# BEP2_rev1_seeed.net
KiCad netlist of a schematic drawn in EAGLE
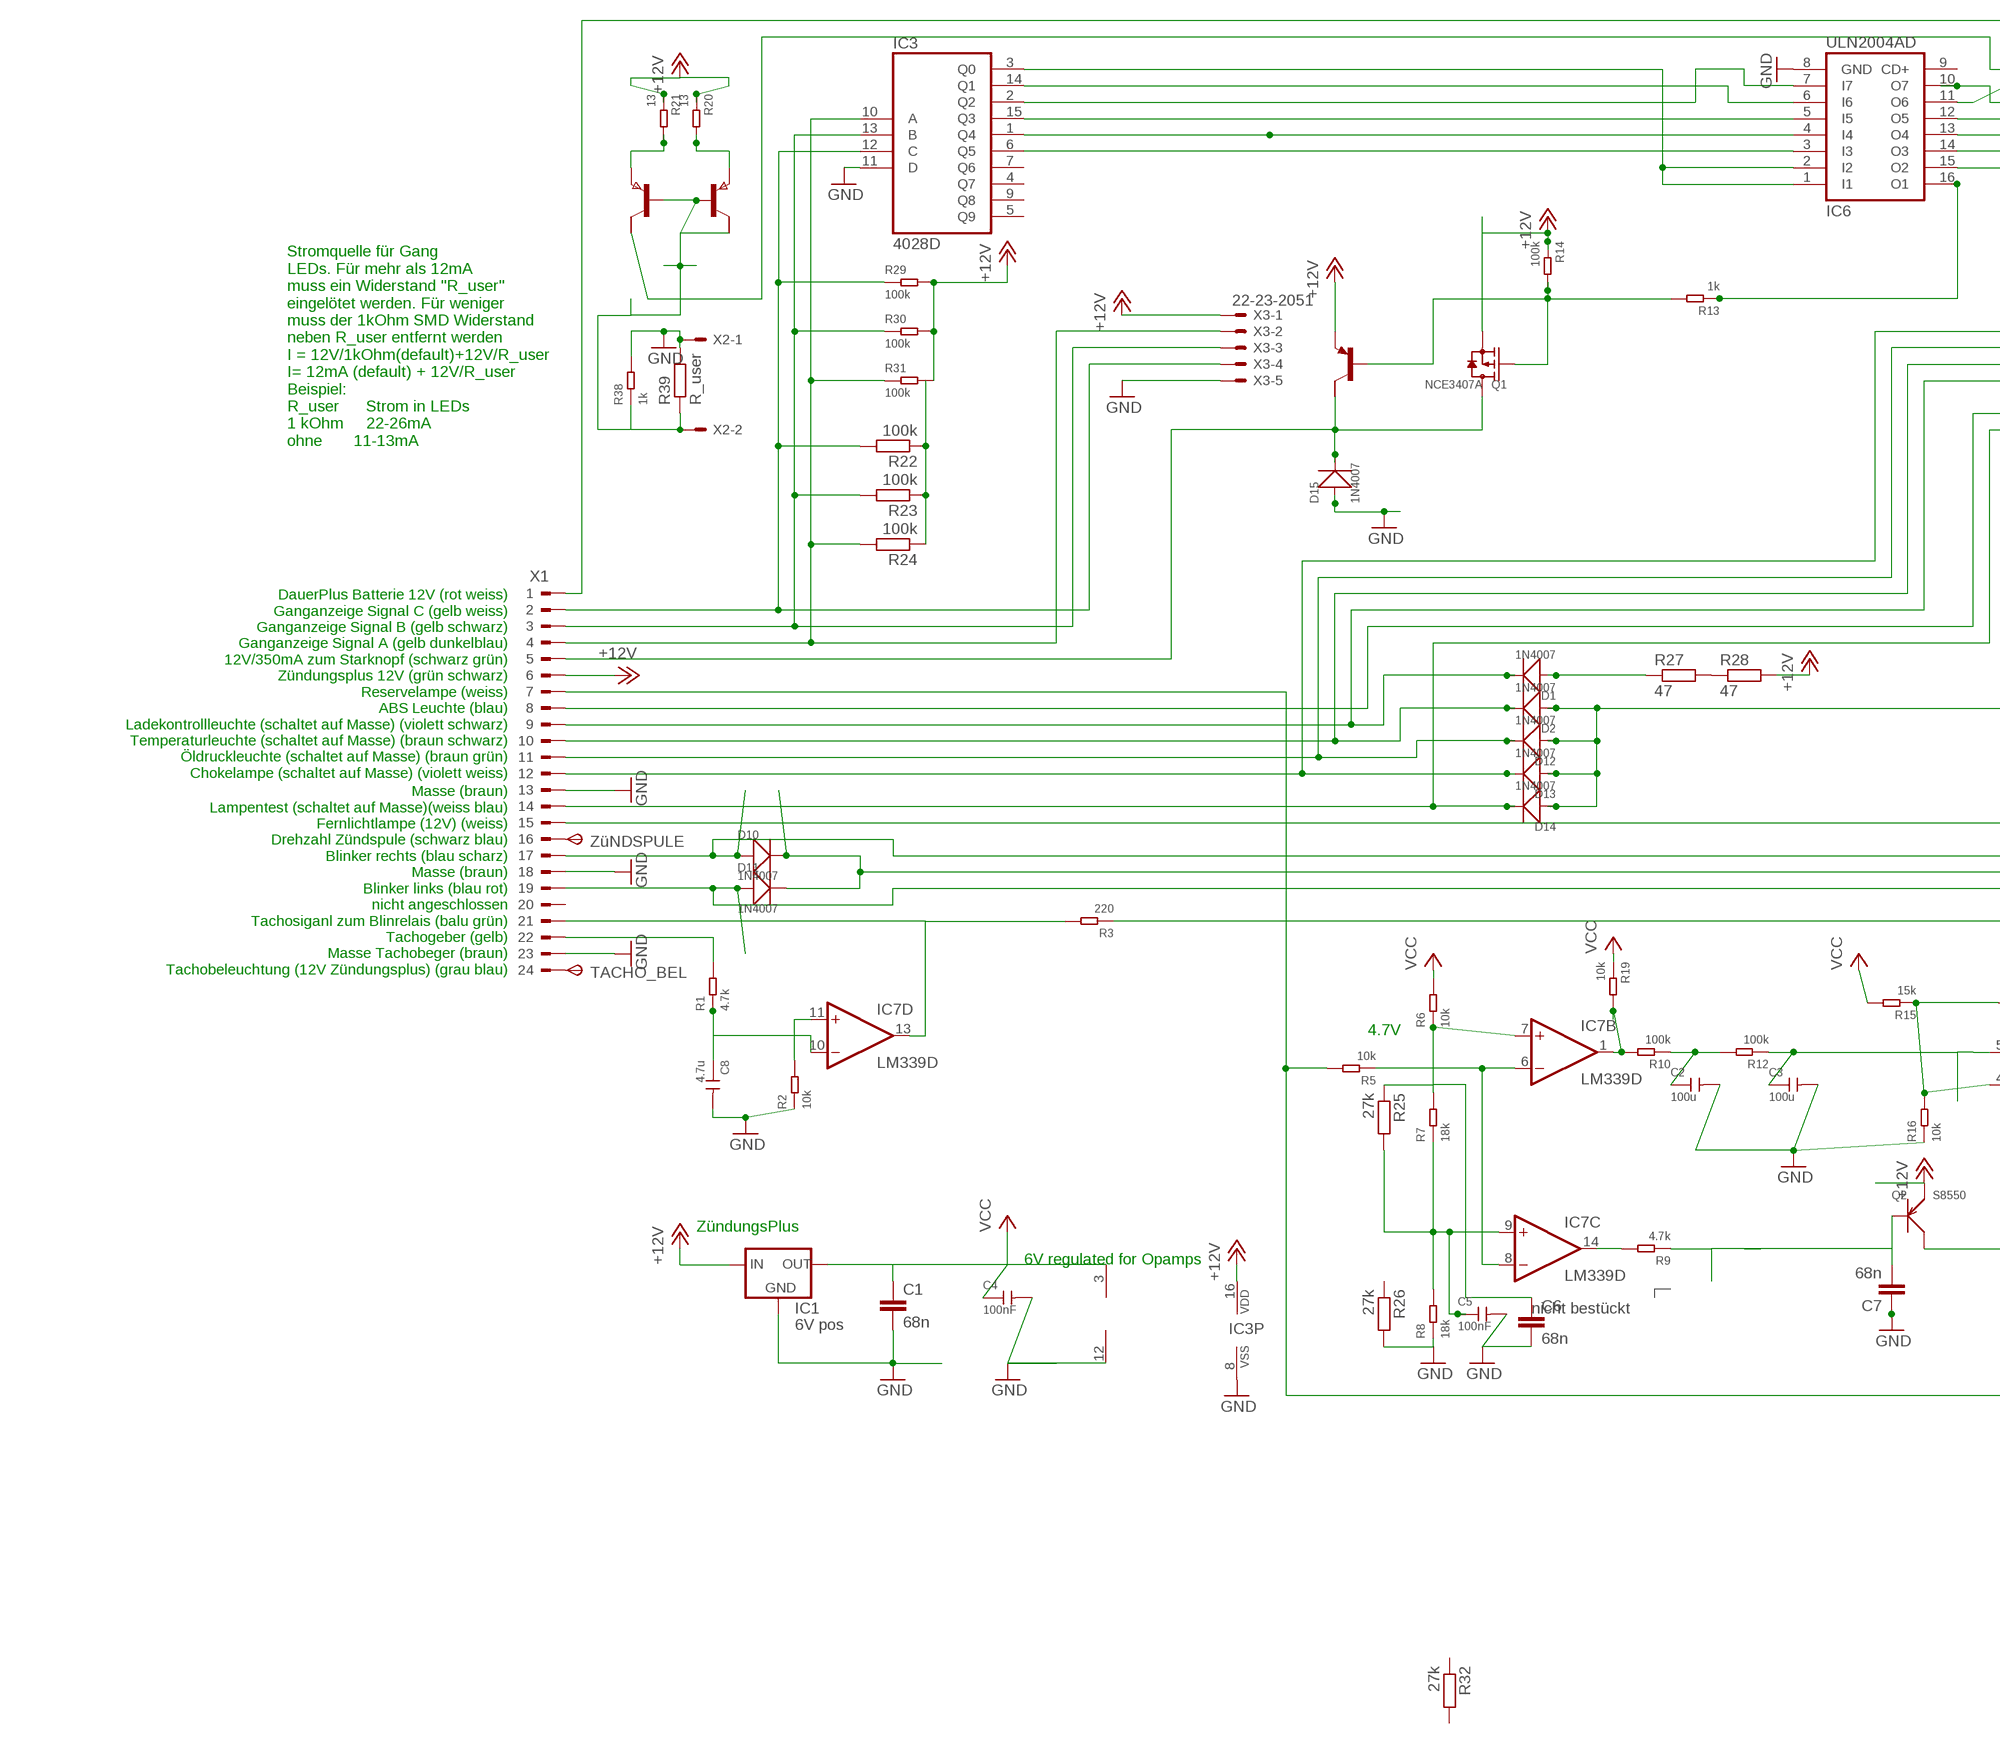
[diagram p0: schematic, sheet 1, part 1 of 2]
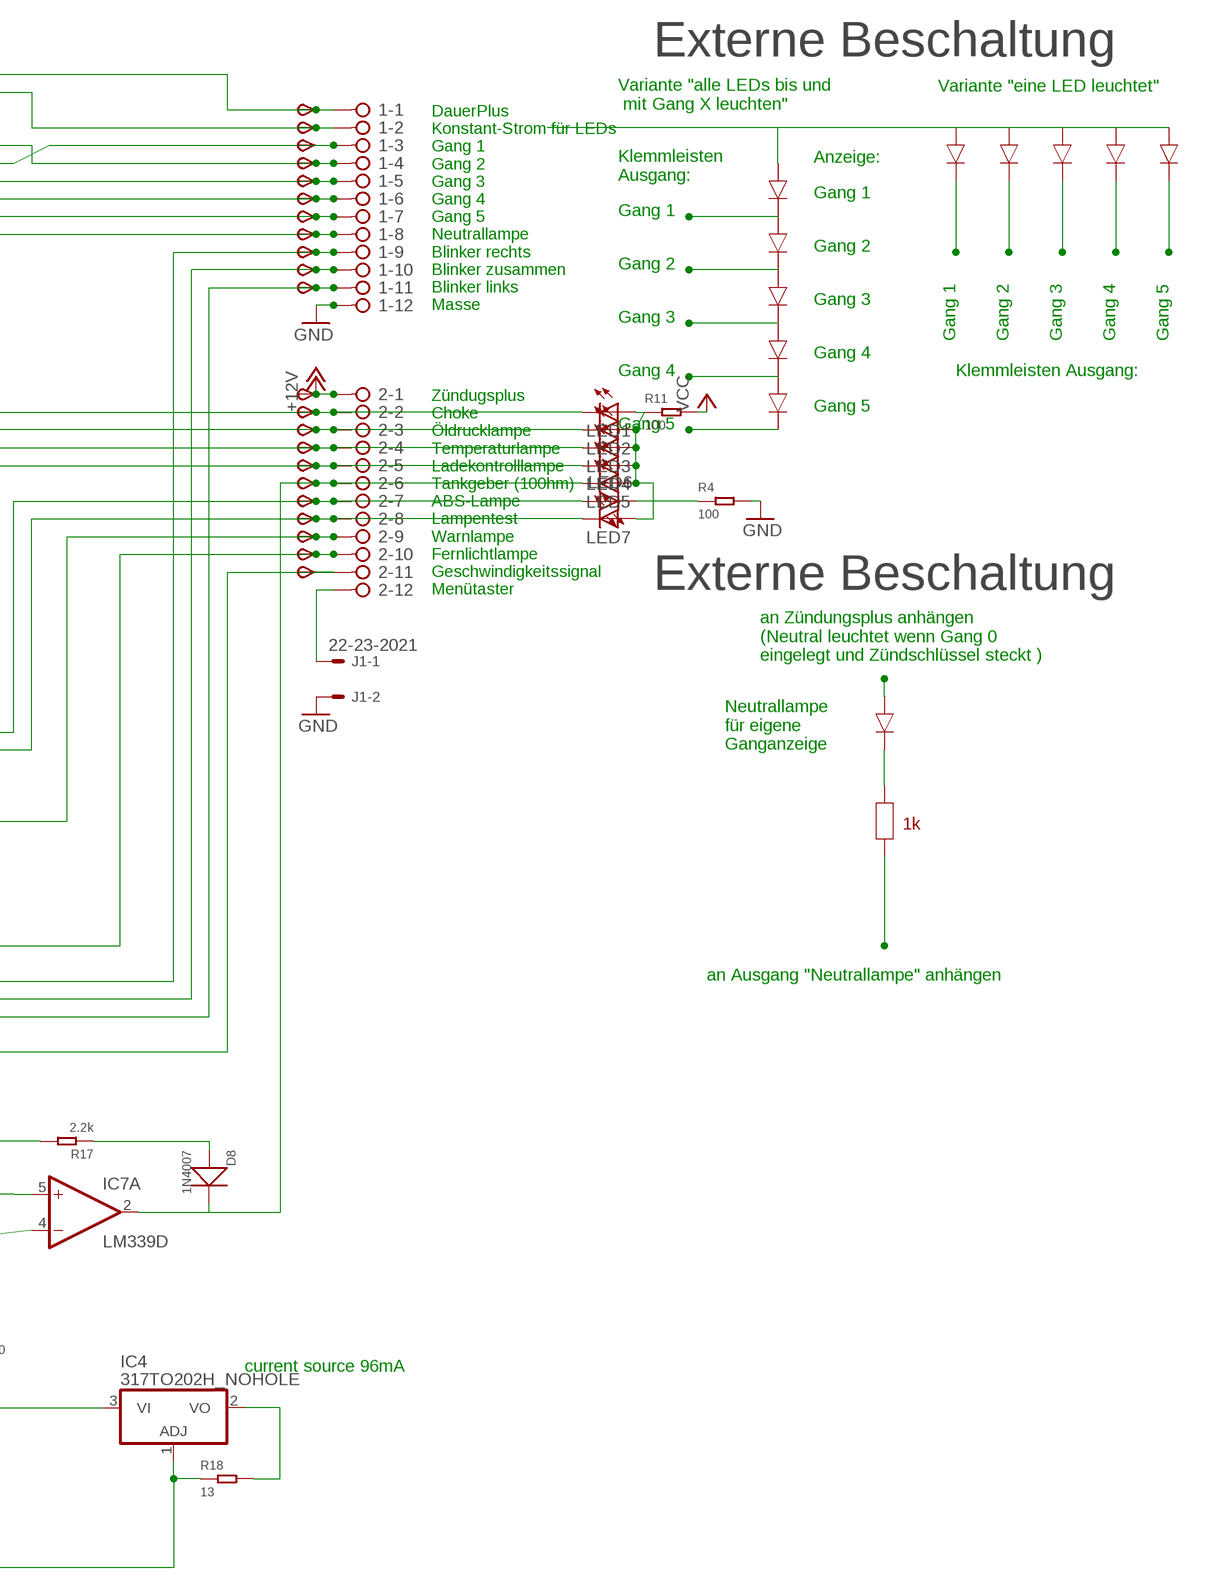
[diagram p1: schematic, sheet 1, part 2 of 2]

(export (version "E")
  (design (tool "Eeschema 10.0.6"))
  (components
    (comp (ref "1")
      (value "2081-1132")
      (footprint "eagle-import:12-PIN")
      (libsource (lib "eagle-import") (part "2081-1132"))
    )
    (comp (ref "2")
      (value "2081-1132")
      (footprint "eagle-import:12-PIN")
      (libsource (lib "eagle-import") (part "2081-1132"))
    )
    (comp (ref "C1")
      (value "68n")
      (footprint "eagle-import:C1206K")
      (libsource (lib "eagle-import") (part "C-EUC1206K"))
    )
    (comp (ref "C2")
      (value "100u")
      (footprint "eagle-import:C1206")
      (fields (field (name "MPN") "GRM31CR60J107ME39L"))
      (libsource (lib "eagle-import") (part "CERAMIC-100UF-6.3V-20%-X5R(1206)"))
    )
    (comp (ref "C3")
      (value "100u")
      (footprint "eagle-import:C1206")
      (fields (field (name "MPN") "GRM31CR60J107ME39L"))
      (libsource (lib "eagle-import") (part "CERAMIC-100UF-6.3V-20%-X5R(1206)"))
    )
    (comp (ref "C4")
      (value "100nF")
      (footprint "eagle-import:C0805")
      (fields (field (name "MPN") "CC0805KRX7R9BB104"))
      (libsource (lib "eagle-import") (part "CERAMIC-100NF-50V-10%-X7R(0805)"))
    )
    (comp (ref "C5")
      (value "100nF")
      (footprint "eagle-import:C0805")
      (fields (field (name "MPN") "CC0805KRX7R9BB104"))
      (libsource (lib "eagle-import") (part "CERAMIC-100NF-50V-10%-X7R(0805)"))
    )
    (comp (ref "C6")
      (value "68n")
      (footprint "eagle-import:C1206K")
      (libsource (lib "eagle-import") (part "C-EUC1206K"))
    )
    (comp (ref "C7")
      (value "68n")
      (footprint "eagle-import:C1206K")
      (libsource (lib "eagle-import") (part "C-EUC1206K"))
    )
    (comp (ref "C8")
      (value "4.7u")
      (footprint "eagle-import:C0805")
      (fields (field (name "MPN") "CC0805KKX5R8BB475"))
      (libsource (lib "eagle-import") (part "CERAMIC-4.7UF-25V-10%-X5R(0805)"))
    )
    (comp (ref "D1")
      (value "1N4007")
      (footprint "eagle-import:DO-214AC")
      (libsource (lib "eagle-import") (part "DIODE-GEN-PURPOSE-1KV-1A(DO-214AC)"))
    )
    (comp (ref "D2")
      (value "1N4007")
      (footprint "eagle-import:DO-214AC")
      (libsource (lib "eagle-import") (part "DIODE-GEN-PURPOSE-1KV-1A(DO-214AC)"))
    )
    (comp (ref "D8")
      (value "1N4007")
      (footprint "eagle-import:DO-214AC")
      (libsource (lib "eagle-import") (part "DIODE-GEN-PURPOSE-1KV-1A(DO-214AC)"))
    )
    (comp (ref "D10")
      (value "1N4007")
      (footprint "eagle-import:DO-214AC")
      (libsource (lib "eagle-import") (part "DIODE-GEN-PURPOSE-1KV-1A(DO-214AC)"))
    )
    (comp (ref "D11")
      (value "1N4007")
      (footprint "eagle-import:DO-214AC")
      (libsource (lib "eagle-import") (part "DIODE-GEN-PURPOSE-1KV-1A(DO-214AC)"))
    )
    (comp (ref "D12")
      (value "1N4007")
      (footprint "eagle-import:DO-214AC")
      (libsource (lib "eagle-import") (part "DIODE-GEN-PURPOSE-1KV-1A(DO-214AC)"))
    )
    (comp (ref "D13")
      (value "1N4007")
      (footprint "eagle-import:DO-214AC")
      (libsource (lib "eagle-import") (part "DIODE-GEN-PURPOSE-1KV-1A(DO-214AC)"))
    )
    (comp (ref "D14")
      (value "1N4007")
      (footprint "eagle-import:DO-214AC")
      (libsource (lib "eagle-import") (part "DIODE-GEN-PURPOSE-1KV-1A(DO-214AC)"))
    )
    (comp (ref "D15")
      (value "1N4007")
      (footprint "eagle-import:DO-214AC")
      (libsource (lib "eagle-import") (part "DIODE-GEN-PURPOSE-1KV-1A(DO-214AC)"))
    )
    (comp (ref "IC1")
      (value "6V pos")
      (footprint "eagle-import:78LXX")
      (libsource (lib "eagle-import") (part "78LXX"))
    )
    (comp (ref "IC3")
      (value "4028D")
      (footprint "eagle-import:SO16")
      (libsource (lib "eagle-import") (part "4028D"))
    )
    (comp (ref "IC4")
      (value "317TO202H_NOHOLE")
      (footprint "eagle-import:TO220H_NOHOLE")
      (libsource (lib "eagle-import") (part "317TO202H_NOHOLE"))
    )
    (comp (ref "IC6")
      (value "ULN2004AD")
      (footprint "eagle-import:SO16")
      (libsource (lib "eagle-import") (part "ULN2004AD"))
    )
    (comp (ref "IC7")
      (value "LM339D")
      (footprint "eagle-import:SO14")
      (libsource (lib "eagle-import") (part "LM339D"))
    )
    (comp (ref "J1")
      (value "22-23-2021")
      (footprint "eagle-import:22-23-2021")
      (fields (field (name "MF") "MOLEX"))
      (libsource (lib "eagle-import") (part "con_Molex_BMW_22-23-2021"))
    )
    (comp (ref "LED1")
      (value "LEDLD260")
      (footprint "eagle-import:LD260")
      (libsource (lib "eagle-import") (part "LEDLD260"))
    )
    (comp (ref "LED2")
      (value "LEDLD260")
      (footprint "eagle-import:LD260")
      (libsource (lib "eagle-import") (part "LEDLD260"))
    )
    (comp (ref "LED3")
      (value "LEDLD260")
      (footprint "eagle-import:LD260")
      (libsource (lib "eagle-import") (part "LEDLD260"))
    )
    (comp (ref "LED4")
      (value "LEDLD260")
      (footprint "eagle-import:LD260")
      (libsource (lib "eagle-import") (part "LEDLD260"))
    )
    (comp (ref "LED5")
      (value "LEDLD260")
      (footprint "eagle-import:LD260")
      (libsource (lib "eagle-import") (part "LEDLD260"))
    )
    (comp (ref "LED6")
      (value "LEDLD260")
      (footprint "eagle-import:LD260")
      (libsource (lib "eagle-import") (part "LEDLD260"))
    )
    (comp (ref "LED7")
      (value "LEDLD260")
      (footprint "eagle-import:LD260")
      (libsource (lib "eagle-import") (part "LEDLD260"))
    )
    (comp (ref "Q1")
      (value "NCE3407A")
      (footprint "eagle-import:SOT-23")
      (libsource (lib "eagle-import") (part "SMD-MOSFET-P-CH-VDC=30V-ID=4.3A-NCE3407A(SOT-23)"))
    )
    (comp (ref "Q2")
      (value "S8550")
      (footprint "eagle-import:SOT-23")
      (libsource (lib "eagle-import") (part "SMD-TRANSISTORS-PNP-25V-500MA-S8550(SOT-23)"))
    )
    (comp (ref "Q3")
      (value "BCP53T1")
      (footprint "eagle-import:SOT223")
      (libsource (lib "eagle-import") (part "BCP53T1"))
    )
    (comp (ref "R1")
      (value "4.7k")
      (footprint "eagle-import:R0805")
      (fields (field (name "MPN") "RC0805JR-074K7L"))
      (libsource (lib "eagle-import") (part "SMD-RES-4.7K-5%-1/8W(0805)"))
    )
    (comp (ref "R2")
      (value "10k")
      (footprint "eagle-import:R0805")
      (fields (field (name "MPN") "RC0805FR-0710KL"))
      (libsource (lib "eagle-import") (part "SMD-RES-10K-1%-1/8W(0805)"))
    )
    (comp (ref "R3")
      (value "220")
      (footprint "eagle-import:R0805")
      (fields (field (name "MPN") "RC0805JR-07220RL"))
      (libsource (lib "eagle-import") (part "SMD-RES-220R-5%-1/8W(0805)"))
    )
    (comp (ref "R4")
      (value "100")
      (footprint "eagle-import:R0805")
      (fields (field (name "MPN") "RC0805JR-07100RL"))
      (libsource (lib "eagle-import") (part "SMD-RES-100R-5%-1/8W(0805)"))
    )
    (comp (ref "R5")
      (value "10k")
      (footprint "eagle-import:R0805")
      (fields (field (name "MPN") "RC0805FR-0710KL"))
      (libsource (lib "eagle-import") (part "SMD-RES-10K-1%-1/8W(0805)"))
    )
    (comp (ref "R6")
      (value "10k")
      (footprint "eagle-import:R0805")
      (fields (field (name "MPN") "RC0805FR-0710KL"))
      (libsource (lib "eagle-import") (part "SMD-RES-10K-1%-1/8W(0805)"))
    )
    (comp (ref "R7")
      (value "18k")
      (footprint "eagle-import:R0603")
      (fields (field (name "MPN") "RC0603JR-0718KL"))
      (libsource (lib "eagle-import") (part "SMD-RES-18K-5%-1/10W(0603)"))
    )
    (comp (ref "R8")
      (value "18k")
      (footprint "eagle-import:R0603")
      (fields (field (name "MPN") "RC0603JR-0718KL"))
      (libsource (lib "eagle-import") (part "SMD-RES-18K-5%-1/10W(0603)"))
    )
    (comp (ref "R9")
      (value "4.7k")
      (footprint "eagle-import:R0805")
      (fields (field (name "MPN") "RC0805JR-074K7L"))
      (libsource (lib "eagle-import") (part "SMD-RES-4.7K-5%-1/8W(0805)"))
    )
    (comp (ref "R10")
      (value "100k")
      (footprint "eagle-import:R0603")
      (fields (field (name "MPN") "RC0603FR-07100KL"))
      (libsource (lib "eagle-import") (part "SMD-RES-100K-1%-1/10W(0603)"))
    )
    (comp (ref "R11")
      (value "100")
      (footprint "eagle-import:R0805")
      (fields (field (name "MPN") "RC0805JR-07100RL"))
      (libsource (lib "eagle-import") (part "SMD-RES-100R-5%-1/8W(0805)"))
    )
    (comp (ref "R12")
      (value "100k")
      (footprint "eagle-import:R0603")
      (fields (field (name "MPN") "RC0603FR-07100KL"))
      (libsource (lib "eagle-import") (part "SMD-RES-100K-1%-1/10W(0603)"))
    )
    (comp (ref "R13")
      (value "1k")
      (footprint "eagle-import:R0805")
      (fields (field (name "MPN") "RC0805JR-071KL"))
      (libsource (lib "eagle-import") (part "SMD-RES-1K-5%-1/8W(0805)"))
    )
    (comp (ref "R14")
      (value "100k")
      (footprint "eagle-import:R0603")
      (fields (field (name "MPN") "RC0603FR-07100KL"))
      (libsource (lib "eagle-import") (part "SMD-RES-100K-1%-1/10W(0603)"))
    )
    (comp (ref "R15")
      (value "15k")
      (footprint "eagle-import:R0603")
      (fields (field (name "MPN") "RC0603FR-0715KL"))
      (libsource (lib "eagle-import") (part "SMD-RES-15K-1%-1/10W(0603)"))
    )
    (comp (ref "R16")
      (value "10k")
      (footprint "eagle-import:R0805")
      (fields (field (name "MPN") "RC0805FR-0710KL"))
      (libsource (lib "eagle-import") (part "SMD-RES-10K-1%-1/8W(0805)"))
    )
    (comp (ref "R17")
      (value "2.2k")
      (footprint "eagle-import:R0805")
      (fields (field (name "MPN") "RC0805JR-072K2L"))
      (libsource (lib "eagle-import") (part "SMD-RES-2.2K-5%-1/8W(0805)"))
    )
    (comp (ref "R18")
      (value "13")
      (footprint "eagle-import:R1206")
      (fields (field (name "MPN") "RC1206JR-0713RL"))
      (libsource (lib "eagle-import") (part "SMD-RES-13R-5%-1/4W(1206)"))
    )
    (comp (ref "R19")
      (value "10k")
      (footprint "eagle-import:R0805")
      (fields (field (name "MPN") "RC0805FR-0710KL"))
      (libsource (lib "eagle-import") (part "SMD-RES-10K-1%-1/8W(0805)"))
    )
    (comp (ref "R20")
      (value "13")
      (footprint "eagle-import:R1206")
      (fields (field (name "MPN") "RC1206JR-0713RL"))
      (libsource (lib "eagle-import") (part "SMD-RES-13R-5%-1/4W(1206)"))
    )
    (comp (ref "R21")
      (value "13")
      (footprint "eagle-import:R1206")
      (fields (field (name "MPN") "RC1206JR-0713RL"))
      (libsource (lib "eagle-import") (part "SMD-RES-13R-5%-1/4W(1206)"))
    )
    (comp (ref "R22")
      (value "100k")
      (footprint "eagle-import:R0805")
      (libsource (lib "eagle-import") (part "R-EU_R0805"))
    )
    (comp (ref "R23")
      (value "100k")
      (footprint "eagle-import:R0805")
      (libsource (lib "eagle-import") (part "R-EU_R0805"))
    )
    (comp (ref "R24")
      (value "100k")
      (footprint "eagle-import:R0805")
      (libsource (lib "eagle-import") (part "R-EU_R0805"))
    )
    (comp (ref "R25")
      (value "27k")
      (footprint "eagle-import:R0805")
      (libsource (lib "eagle-import") (part "R-EU_R0805"))
    )
    (comp (ref "R26")
      (value "27k")
      (footprint "eagle-import:R0805")
      (libsource (lib "eagle-import") (part "R-EU_R0805"))
    )
    (comp (ref "R27")
      (value "47")
      (footprint "eagle-import:V235_17_1MM")
      (libsource (lib "eagle-import") (part "R-EU_V235/17_1MM"))
    )
    (comp (ref "R28")
      (value "47")
      (footprint "eagle-import:V235_17_1MM")
      (libsource (lib "eagle-import") (part "R-EU_V235/17_1MM"))
    )
    (comp (ref "R29")
      (value "100k")
      (footprint "eagle-import:R0603")
      (fields (field (name "MPN") "RC0603FR-07100KL"))
      (libsource (lib "eagle-import") (part "SMD-RES-100K-1%-1/10W(0603)"))
    )
    (comp (ref "R30")
      (value "100k")
      (footprint "eagle-import:R0603")
      (fields (field (name "MPN") "RC0603FR-07100KL"))
      (libsource (lib "eagle-import") (part "SMD-RES-100K-1%-1/10W(0603)"))
    )
    (comp (ref "R31")
      (value "100k")
      (footprint "eagle-import:R0603")
      (fields (field (name "MPN") "RC0603FR-07100KL"))
      (libsource (lib "eagle-import") (part "SMD-RES-100K-1%-1/10W(0603)"))
    )
    (comp (ref "R32")
      (value "27k")
      (footprint "eagle-import:R0805")
      (libsource (lib "eagle-import") (part "R-EU_R0805"))
    )
    (comp (ref "R38")
      (value "1k")
      (footprint "eagle-import:R0805")
      (fields (field (name "MPN") "RC0805JR-071KL"))
      (libsource (lib "eagle-import") (part "SMD-RES-1K-5%-1/8W(0805)"))
    )
    (comp (ref "R39")
      (value "R_user")
      (footprint "eagle-import:R0805")
      (libsource (lib "eagle-import") (part "R-EU_R0805"))
    )
    (comp (ref "T1")
      (value "PNP2SM8")
      (footprint "eagle-import:SM8")
      (libsource (lib "eagle-import") (part "PNP2SM8"))
    )
    (comp (ref "TACHO_BEL")
      (value "TPSP1_1MM")
      (footprint "eagle-import:P1_1.0MM")
      (libsource (lib "eagle-import") (part "TPSP1_1MM"))
    )
    (comp (ref "TP1")
      (value "TPSB1.8")
      (footprint "eagle-import:B1.8")
      (libsource (lib "eagle-import") (part "TPSB1.8"))
    )
    (comp (ref "TP2")
      (value "TPSB1.8")
      (footprint "eagle-import:B1.8")
      (libsource (lib "eagle-import") (part "TPSB1.8"))
    )
    (comp (ref "TP3")
      (value "TPSB1.8")
      (footprint "eagle-import:B1.8")
      (libsource (lib "eagle-import") (part "TPSB1.8"))
    )
    (comp (ref "TP4")
      (value "TPSB1.8")
      (footprint "eagle-import:B1.8")
      (libsource (lib "eagle-import") (part "TPSB1.8"))
    )
    (comp (ref "TP5")
      (value "TPSB1.8")
      (footprint "eagle-import:B1.8")
      (libsource (lib "eagle-import") (part "TPSB1.8"))
    )
    (comp (ref "TP6")
      (value "TPSB1.8")
      (footprint "eagle-import:B1.8")
      (libsource (lib "eagle-import") (part "TPSB1.8"))
    )
    (comp (ref "TP7")
      (value "TPSB1.8")
      (footprint "eagle-import:B1.8")
      (libsource (lib "eagle-import") (part "TPSB1.8"))
    )
    (comp (ref "TP8")
      (value "TPSB1.8")
      (footprint "eagle-import:B1.8")
      (libsource (lib "eagle-import") (part "TPSB1.8"))
    )
    (comp (ref "TP9")
      (value "TPSB1.8")
      (footprint "eagle-import:B1.8")
      (libsource (lib "eagle-import") (part "TPSB1.8"))
    )
    (comp (ref "TP10")
      (value "TPSB1.8")
      (footprint "eagle-import:B1.8")
      (libsource (lib "eagle-import") (part "TPSB1.8"))
    )
    (comp (ref "TP11")
      (value "TPSB1.8")
      (footprint "eagle-import:B1.8")
      (libsource (lib "eagle-import") (part "TPSB1.8"))
    )
    (comp (ref "TP12")
      (value "TPSB1.8")
      (footprint "eagle-import:B1.8")
      (libsource (lib "eagle-import") (part "TPSB1.8"))
    )
    (comp (ref "TP16")
      (value "TPSB1.8")
      (footprint "eagle-import:B1.8")
      (libsource (lib "eagle-import") (part "TPSB1.8"))
    )
    (comp (ref "TP17")
      (value "TPSB1.8")
      (footprint "eagle-import:B1.8")
      (libsource (lib "eagle-import") (part "TPSB1.8"))
    )
    (comp (ref "TP18")
      (value "TPSB1.8")
      (footprint "eagle-import:B1.8")
      (libsource (lib "eagle-import") (part "TPSB1.8"))
    )
    (comp (ref "TP19")
      (value "TPSB1.8")
      (footprint "eagle-import:B1.8")
      (libsource (lib "eagle-import") (part "TPSB1.8"))
    )
    (comp (ref "TP21")
      (value "TPSB1.8")
      (footprint "eagle-import:B1.8")
      (libsource (lib "eagle-import") (part "TPSB1.8"))
    )
    (comp (ref "TP22")
      (value "TPSB1.8")
      (footprint "eagle-import:B1.8")
      (libsource (lib "eagle-import") (part "TPSB1.8"))
    )
    (comp (ref "TP23")
      (value "TPSB1.8")
      (footprint "eagle-import:B1.8")
      (libsource (lib "eagle-import") (part "TPSB1.8"))
    )
    (comp (ref "TP24")
      (value "TPSB1,27")
      (footprint "eagle-import:B1,27")
      (libsource (lib "eagle-import") (part "TPSB1,27"))
    )
    (comp (ref "TP25")
      (value "TPSB1.8")
      (footprint "eagle-import:B1.8")
      (libsource (lib "eagle-import") (part "TPSB1.8"))
    )
    (comp (ref "TP26")
      (value "TPSB1.8")
      (footprint "eagle-import:B1.8")
      (libsource (lib "eagle-import") (part "TPSB1.8"))
    )
    (comp (ref "X1")
      (value "CON_BMW")
      (footprint "eagle-import:24-PIN")
      (libsource (lib "eagle-import") (part "CON_BMW"))
    )
    (comp (ref "X2")
      (value "22-23-2021")
      (footprint "eagle-import:22-23-2021")
      (fields (field (name "MF") "MOLEX"))
      (libsource (lib "eagle-import") (part "22-23-2021"))
    )
    (comp (ref "X3")
      (value "22-23-2051")
      (footprint "eagle-import:22-23-2051")
      (fields (field (name "MF") "MOLEX"))
      (libsource (lib "eagle-import") (part "22-23-2051"))
    )
    (comp (ref "ZüNDSPULE")
      (value "TPSP1_1MM")
      (footprint "eagle-import:P1_1.0MM")
      (libsource (lib "eagle-import") (part "TPSP1_1MM"))
    )
  )
  (nets
    (net (code "1") (name "+12V") (class "Default")
      (node (ref "2") (pin "1") (pinfunction "KL_1") (pintype "passive"))
      (node (ref "IC1") (pin "IN") (pinfunction "IN_IN") (pintype "input"))
      (node (ref "IC3") (pin "16") (pinfunction "VDD_16") (pintype "power_in"))
      (node (ref "Q1") (pin "2") (pinfunction "S_2") (pintype "passive"))
      (node (ref "Q2") (pin "2") (pinfunction "E_2") (pintype "passive"))
      (node (ref "Q3") (pin "3") (pinfunction "E_3") (pintype "passive"))
      (node (ref "R14") (pin "1") (pinfunction "1_1") (pintype "passive"))
      (node (ref "R20") (pin "1") (pinfunction "1_1") (pintype "passive"))
      (node (ref "R21") (pin "1") (pinfunction "1_1") (pintype "passive"))
      (node (ref "R28") (pin "2") (pinfunction "2_2") (pintype "passive"))
      (node (ref "R29") (pin "2") (pinfunction "2_2") (pintype "passive"))
      (node (ref "R30") (pin "2") (pinfunction "2_2") (pintype "passive"))
      (node (ref "R31") (pin "2") (pinfunction "2_2") (pintype "passive"))
      (node (ref "TP12") (pin "TP") (pinfunction "PP_TP") (pintype "input"))
      (node (ref "X1") (pin "6") (pinfunction "6_6") (pintype "passive"))
      (node (ref "X3") (pin "1") (pinfunction "S_1") (pintype "passive"))
    )
    (net (code "2") (name "GND") (class "Default")
      (node (ref "1") (pin "12") (pinfunction "KL_12") (pintype "passive"))
      (node (ref "C1") (pin "2") (pinfunction "2_2") (pintype "passive"))
      (node (ref "C2") (pin "2") (pinfunction "2_2") (pintype "passive"))
      (node (ref "C3") (pin "2") (pinfunction "2_2") (pintype "passive"))
      (node (ref "C4") (pin "2") (pinfunction "2_2") (pintype "passive"))
      (node (ref "C5") (pin "2") (pinfunction "2_2") (pintype "passive"))
      (node (ref "C6") (pin "2") (pinfunction "2_2") (pintype "passive"))
      (node (ref "C7") (pin "1") (pinfunction "1_1") (pintype "passive"))
      (node (ref "C8") (pin "2") (pinfunction "2_2") (pintype "passive"))
      (node (ref "D15") (pin "1") (pinfunction "+_1") (pintype "passive"))
      (node (ref "IC1") (pin "GND") (pinfunction "GND_GND") (pintype "input"))
      (node (ref "IC3") (pin "11") (pinfunction "D_11") (pintype "input"))
      (node (ref "IC3") (pin "8") (pinfunction "VSS_8") (pintype "power_in"))
      (node (ref "IC6") (pin "8") (pinfunction "GND_8") (pintype "power_in"))
      (node (ref "IC7") (pin "12") (pinfunction "GND_12") (pintype "power_in"))
      (node (ref "J1") (pin "2") (pinfunction "S_2") (pintype "passive"))
      (node (ref "R16") (pin "1") (pinfunction "1_1") (pintype "passive"))
      (node (ref "R2") (pin "1") (pinfunction "1_1") (pintype "passive"))
      (node (ref "R26") (pin "2") (pinfunction "2_2") (pintype "passive"))
      (node (ref "R38") (pin "2") (pinfunction "2_2") (pintype "passive"))
      (node (ref "R39") (pin "2") (pinfunction "2_2") (pintype "passive"))
      (node (ref "R4") (pin "2") (pinfunction "2_2") (pintype "passive"))
      (node (ref "R8") (pin "1") (pinfunction "1_1") (pintype "passive"))
      (node (ref "X1") (pin "13") (pinfunction "13_13") (pintype "passive"))
      (node (ref "X1") (pin "18") (pinfunction "18_18") (pintype "passive"))
      (node (ref "X1") (pin "23") (pinfunction "23_23") (pintype "passive"))
      (node (ref "X2") (pin "1") (pinfunction "S_1") (pintype "passive"))
      (node (ref "X3") (pin "5") (pinfunction "S_5") (pintype "passive"))
    )
    (net (code "3") (name "Net-(1A-KL)") (class "Default")
      (node (ref "1") (pin "1") (pinfunction "KL_1") (pintype "passive"))
      (node (ref "TP1") (pin "TP") (pinfunction "PP_TP") (pintype "input"))
      (node (ref "X1") (pin "1") (pinfunction "1_1") (pintype "passive"))
    )
    (net (code "4") (name "Net-(1B-KL)") (class "Default")
      (node (ref "1") (pin "10") (pinfunction "KL_10") (pintype "passive"))
      (node (ref "D10") (pin "2") (pinfunction "-_2") (pintype "passive"))
      (node (ref "D11") (pin "2") (pinfunction "-_2") (pintype "passive"))
      (node (ref "TP10") (pin "TP") (pinfunction "PP_TP") (pintype "input"))
    )
    (net (code "5") (name "Net-(1C-KL)") (class "Default")
      (node (ref "1") (pin "11") (pinfunction "KL_11") (pintype "passive"))
      (node (ref "D11") (pin "1") (pinfunction "+_1") (pintype "passive"))
      (node (ref "TP11") (pin "TP") (pinfunction "PP_TP") (pintype "input"))
      (node (ref "X1") (pin "19") (pinfunction "19_19") (pintype "passive"))
    )
    (net (code "6") (name "Net-(1E-KL)") (class "Default")
      (node (ref "1") (pin "2") (pinfunction "KL_2") (pintype "passive"))
      (node (ref "T1") (pin "8") (pinfunction "C1_8") (pintype "passive"))
      (node (ref "TP2") (pin "TP") (pinfunction "PP_TP") (pintype "input"))
    )
    (net (code "7") (name "Net-(1F-KL)") (class "Default")
      (node (ref "1") (pin "3") (pinfunction "KL_3") (pintype "passive"))
      (node (ref "IC6") (pin "11") (pinfunction "O6_11") (pintype "open_collector"))
      (node (ref "TP3") (pin "TP") (pinfunction "PP_TP") (pintype "input"))
    )
    (net (code "8") (name "Net-(1G-KL)") (class "Default")
      (node (ref "1") (pin "4") (pinfunction "KL_4") (pintype "passive"))
      (node (ref "IC6") (pin "10") (pinfunction "O7_10") (pintype "open_collector"))
      (node (ref "TP4") (pin "TP") (pinfunction "PP_TP") (pintype "input"))
    )
    (net (code "9") (name "Net-(1H-KL)") (class "Default")
      (node (ref "1") (pin "5") (pinfunction "KL_5") (pintype "passive"))
      (node (ref "IC6") (pin "12") (pinfunction "O5_12") (pintype "open_collector"))
      (node (ref "TP5") (pin "TP") (pinfunction "PP_TP") (pintype "input"))
    )
    (net (code "10") (name "Net-(1I-KL)") (class "Default")
      (node (ref "1") (pin "6") (pinfunction "KL_6") (pintype "passive"))
      (node (ref "IC6") (pin "13") (pinfunction "O4_13") (pintype "open_collector"))
      (node (ref "TP6") (pin "TP") (pinfunction "PP_TP") (pintype "input"))
    )
    (net (code "11") (name "Net-(1J-KL)") (class "Default")
      (node (ref "1") (pin "7") (pinfunction "KL_7") (pintype "passive"))
      (node (ref "IC6") (pin "14") (pinfunction "O3_14") (pintype "open_collector"))
      (node (ref "TP7") (pin "TP") (pinfunction "PP_TP") (pintype "input"))
    )
    (net (code "12") (name "Net-(1K-KL)") (class "Default")
      (node (ref "1") (pin "8") (pinfunction "KL_8") (pintype "passive"))
      (node (ref "IC6") (pin "15") (pinfunction "O2_15") (pintype "open_collector"))
      (node (ref "TP8") (pin "TP") (pinfunction "PP_TP") (pintype "input"))
    )
    (net (code "13") (name "Net-(1L-KL)") (class "Default")
      (node (ref "1") (pin "9") (pinfunction "KL_9") (pintype "passive"))
      (node (ref "D10") (pin "1") (pinfunction "+_1") (pintype "passive"))
      (node (ref "TP9") (pin "TP") (pinfunction "PP_TP") (pintype "input"))
      (node (ref "X1") (pin "17") (pinfunction "17_17") (pintype "passive"))
    )
    (net (code "14") (name "Net-(2B-KL)") (class "Default")
      (node (ref "2") (pin "10") (pinfunction "KL_10") (pintype "passive"))
      (node (ref "TP25") (pin "TP") (pinfunction "PP_TP") (pintype "input"))
      (node (ref "X1") (pin "15") (pinfunction "15_15") (pintype "passive"))
    )
    (net (code "15") (name "Net-(2C-KL)") (class "Default")
      (node (ref "2") (pin "11") (pinfunction "KL_11") (pintype "passive"))
      (node (ref "R3") (pin "1") (pinfunction "1_1") (pintype "passive"))
      (node (ref "TP26") (pin "TP") (pinfunction "PP_TP") (pintype "input"))
    )
    (net (code "16") (name "Net-(2D-KL)") (class "Default")
      (node (ref "2") (pin "12") (pinfunction "KL_12") (pintype "passive"))
      (node (ref "J1") (pin "1") (pinfunction "S_1") (pintype "passive"))
    )
    (net (code "17") (name "Net-(2E-KL)") (class "Default")
      (node (ref "2") (pin "2") (pinfunction "KL_2") (pintype "passive"))
      (node (ref "D13") (pin "2") (pinfunction "-_2") (pintype "passive"))
      (node (ref "LED1") (pin "K") (pinfunction "C_K") (pintype "passive"))
      (node (ref "TP16") (pin "TP") (pinfunction "PP_TP") (pintype "input"))
      (node (ref "X1") (pin "12") (pinfunction "12_12") (pintype "passive"))
    )
    (net (code "18") (name "Net-(2F-KL)") (class "Default")
      (node (ref "2") (pin "3") (pinfunction "KL_3") (pintype "passive"))
      (node (ref "D12") (pin "2") (pinfunction "-_2") (pintype "passive"))
      (node (ref "LED2") (pin "K") (pinfunction "C_K") (pintype "passive"))
      (node (ref "TP17") (pin "TP") (pinfunction "PP_TP") (pintype "input"))
      (node (ref "X1") (pin "11") (pinfunction "11_11") (pintype "passive"))
    )
    (net (code "19") (name "Net-(2G-KL)") (class "Default")
      (node (ref "2") (pin "4") (pinfunction "KL_4") (pintype "passive"))
      (node (ref "D2") (pin "2") (pinfunction "-_2") (pintype "passive"))
      (node (ref "LED3") (pin "K") (pinfunction "C_K") (pintype "passive"))
      (node (ref "TP18") (pin "TP") (pinfunction "PP_TP") (pintype "input"))
      (node (ref "X1") (pin "10") (pinfunction "10_10") (pintype "passive"))
    )
    (net (code "20") (name "Net-(2H-KL)") (class "Default")
      (node (ref "2") (pin "5") (pinfunction "KL_5") (pintype "passive"))
      (node (ref "D1") (pin "2") (pinfunction "-_2") (pintype "passive"))
      (node (ref "LED4") (pin "K") (pinfunction "C_K") (pintype "passive"))
      (node (ref "TP19") (pin "TP") (pinfunction "PP_TP") (pintype "input"))
      (node (ref "X1") (pin "9") (pinfunction "9_9") (pintype "passive"))
    )
    (net (code "21") (name "Net-(2I-KL)") (class "Default")
      (node (ref "2") (pin "6") (pinfunction "KL_6") (pintype "passive"))
      (node (ref "D8") (pin "2") (pinfunction "-_2") (pintype "passive"))
      (node (ref "IC7") (pin "2") (pinfunction "OUT_2") (pintype "open_collector"))
      (node (ref "LED5") (pin "K") (pinfunction "C_K") (pintype "passive"))
      (node (ref "TP21") (pin "TP") (pinfunction "PP_TP") (pintype "input"))
    )
    (net (code "22") (name "Net-(2J-KL)") (class "Default")
      (node (ref "2") (pin "7") (pinfunction "KL_7") (pintype "passive"))
      (node (ref "LED6") (pin "A") (pinfunction "A_A") (pintype "passive"))
      (node (ref "TP22") (pin "TP") (pinfunction "PP_TP") (pintype "input"))
      (node (ref "X1") (pin "8") (pinfunction "8_8") (pintype "passive"))
    )
    (net (code "23") (name "Net-(2K-KL)") (class "Default")
      (node (ref "2") (pin "8") (pinfunction "KL_8") (pintype "passive"))
      (node (ref "D14") (pin "2") (pinfunction "-_2") (pintype "passive"))
      (node (ref "LED7") (pin "K") (pinfunction "C_K") (pintype "passive"))
      (node (ref "TP23") (pin "TP") (pinfunction "PP_TP") (pintype "input"))
      (node (ref "X1") (pin "14") (pinfunction "14_14") (pintype "passive"))
    )
    (net (code "24") (name "Net-(2L-KL)") (class "Default")
      (node (ref "2") (pin "9") (pinfunction "KL_9") (pintype "passive"))
      (node (ref "D12") (pin "1") (pinfunction "+_1") (pintype "passive"))
      (node (ref "D13") (pin "1") (pinfunction "+_1") (pintype "passive"))
      (node (ref "D14") (pin "1") (pinfunction "+_1") (pintype "passive"))
      (node (ref "D2") (pin "1") (pinfunction "+_1") (pintype "passive"))
      (node (ref "TP24") (pin "TP") (pinfunction "PP_TP") (pintype "input"))
    )
    (net (code "25") (name "Net-(C2-Pad1)") (class "Default")
      (node (ref "C2") (pin "1") (pinfunction "1_1") (pintype "passive"))
      (node (ref "R10") (pin "1") (pinfunction "1_1") (pintype "passive"))
      (node (ref "R12") (pin "2") (pinfunction "2_2") (pintype "passive"))
    )
    (net (code "26") (name "Net-(D1-+)") (class "Default")
      (node (ref "D1") (pin "1") (pinfunction "+_1") (pintype "passive"))
      (node (ref "R27") (pin "1") (pinfunction "1_1") (pintype "passive"))
    )
    (net (code "27") (name "Net-(D8-+)") (class "Default")
      (node (ref "D8") (pin "1") (pinfunction "+_1") (pintype "passive"))
      (node (ref "R17") (pin "1") (pinfunction "1_1") (pintype "passive"))
    )
    (net (code "28") (name "Net-(D15--)") (class "Default")
      (node (ref "D15") (pin "2") (pinfunction "-_2") (pintype "passive"))
      (node (ref "Q1") (pin "3") (pinfunction "D_3") (pintype "passive"))
      (node (ref "Q3") (pin "2") (pinfunction "C_2") (pintype "passive"))
      (node (ref "X1") (pin "5") (pinfunction "5_5") (pintype "passive"))
    )
    (net (code "29") (name "Net-(IC3A-A)") (class "Default")
      (node (ref "IC3") (pin "10") (pinfunction "A_10") (pintype "input"))
      (node (ref "R24") (pin "2") (pinfunction "2_2") (pintype "passive"))
      (node (ref "R31") (pin "1") (pinfunction "1_1") (pintype "passive"))
      (node (ref "X1") (pin "4") (pinfunction "4_4") (pintype "passive"))
      (node (ref "X3") (pin "2") (pinfunction "S_2") (pintype "passive"))
    )
    (net (code "30") (name "Net-(IC3A-B)") (class "Default")
      (node (ref "IC3") (pin "13") (pinfunction "B_13") (pintype "input"))
      (node (ref "R23") (pin "2") (pinfunction "2_2") (pintype "passive"))
      (node (ref "R30") (pin "1") (pinfunction "1_1") (pintype "passive"))
      (node (ref "X1") (pin "3") (pinfunction "3_3") (pintype "passive"))
      (node (ref "X3") (pin "3") (pinfunction "S_3") (pintype "passive"))
    )
    (net (code "31") (name "Net-(IC3A-C)") (class "Default")
      (node (ref "IC3") (pin "12") (pinfunction "C_12") (pintype "input"))
      (node (ref "R22") (pin "2") (pinfunction "2_2") (pintype "passive"))
      (node (ref "R29") (pin "1") (pinfunction "1_1") (pintype "passive"))
      (node (ref "X1") (pin "2") (pinfunction "2_2") (pintype "passive"))
      (node (ref "X3") (pin "4") (pinfunction "S_4") (pintype "passive"))
    )
    (net (code "32") (name "Net-(IC3A-Q0)") (class "Default")
      (node (ref "IC3") (pin "3") (pinfunction "Q0_3") (pintype "output"))
      (node (ref "IC6") (pin "1") (pinfunction "I1_1") (pintype "input"))
      (node (ref "IC6") (pin "2") (pinfunction "I2_2") (pintype "input"))
    )
    (net (code "33") (name "Net-(IC3A-Q1)") (class "Default")
      (node (ref "IC3") (pin "14") (pinfunction "Q1_14") (pintype "output"))
      (node (ref "IC6") (pin "6") (pinfunction "I6_6") (pintype "input"))
    )
    (net (code "34") (name "Net-(IC3A-Q2)") (class "Default")
      (node (ref "IC3") (pin "2") (pinfunction "Q2_2") (pintype "output"))
      (node (ref "IC6") (pin "7") (pinfunction "I7_7") (pintype "input"))
    )
    (net (code "35") (name "Net-(IC3A-Q3)") (class "Default")
      (node (ref "IC3") (pin "15") (pinfunction "Q3_15") (pintype "output"))
      (node (ref "IC6") (pin "5") (pinfunction "I5_5") (pintype "input"))
    )
    (net (code "36") (name "Net-(IC3A-Q4)") (class "Default")
      (node (ref "IC3") (pin "1") (pinfunction "Q4_1") (pintype "output"))
      (node (ref "IC6") (pin "4") (pinfunction "I4_4") (pintype "input"))
    )
    (net (code "37") (name "Net-(IC3A-Q5)") (class "Default")
      (node (ref "IC3") (pin "6") (pinfunction "Q5_6") (pintype "output"))
      (node (ref "IC6") (pin "3") (pinfunction "I3_3") (pintype "input"))
    )
    (net (code "38") (name "Net-(IC4-ADJ)") (class "Default")
      (node (ref "IC4") (pin "1") (pinfunction "ADJ_1") (pintype "input"))
      (node (ref "R18") (pin "1") (pinfunction "1_1") (pintype "passive"))
      (node (ref "R5") (pin "2") (pinfunction "2_2") (pintype "passive"))
      (node (ref "X1") (pin "7") (pinfunction "7_7") (pintype "passive"))
    )
    (net (code "39") (name "Net-(IC4-VI)") (class "Default")
      (node (ref "IC4") (pin "3") (pinfunction "VI_3") (pintype "input"))
      (node (ref "Q2") (pin "3") (pinfunction "C_3") (pintype "passive"))
    )
    (net (code "40") (name "Net-(IC4-VO)") (class "Default")
      (node (ref "IC4") (pin "2") (pinfunction "VO_2") (pintype "passive"))
      (node (ref "R18") (pin "2") (pinfunction "2_2") (pintype "passive"))
    )
    (net (code "41") (name "Net-(IC6-O1)") (class "Default")
      (node (ref "IC6") (pin "16") (pinfunction "O1_16") (pintype "open_collector"))
      (node (ref "R13") (pin "1") (pinfunction "1_1") (pintype "passive"))
    )
    (net (code "42") (name "Net-(IC7A-+IN)") (class "Default")
      (node (ref "C3") (pin "1") (pinfunction "1_1") (pintype "passive"))
      (node (ref "IC7") (pin "5") (pinfunction "+IN_5") (pintype "input"))
      (node (ref "R12") (pin "1") (pinfunction "1_1") (pintype "passive"))
    )
    (net (code "43") (name "Net-(IC7A--IN)") (class "Default")
      (node (ref "IC7") (pin "4") (pinfunction "-IN_4") (pintype "input"))
      (node (ref "R15") (pin "1") (pinfunction "1_1") (pintype "passive"))
      (node (ref "R16") (pin "2") (pinfunction "2_2") (pintype "passive"))
      (node (ref "R17") (pin "2") (pinfunction "2_2") (pintype "passive"))
    )
    (net (code "44") (name "Net-(IC7B-+IN)") (class "Default")
      (node (ref "C6") (pin "1") (pinfunction "1_1") (pintype "passive"))
      (node (ref "IC7") (pin "7") (pinfunction "+IN_7") (pintype "input"))
      (node (ref "R25") (pin "1") (pinfunction "1_1") (pintype "passive"))
      (node (ref "R6") (pin "1") (pinfunction "1_1") (pintype "passive"))
      (node (ref "R7") (pin "2") (pinfunction "2_2") (pintype "passive"))
    )
    (net (code "45") (name "Net-(IC7B--IN)") (class "Default")
      (node (ref "IC7") (pin "6") (pinfunction "-IN_6") (pintype "input"))
      (node (ref "IC7") (pin "8") (pinfunction "-IN_8") (pintype "input"))
      (node (ref "R5") (pin "1") (pinfunction "1_1") (pintype "passive"))
    )
    (net (code "46") (name "Net-(IC7B-OUT)") (class "Default")
      (node (ref "IC7") (pin "1") (pinfunction "OUT_1") (pintype "open_collector"))
      (node (ref "R10") (pin "2") (pinfunction "2_2") (pintype "passive"))
      (node (ref "R19") (pin "2") (pinfunction "2_2") (pintype "passive"))
    )
    (net (code "47") (name "Net-(IC7C-+IN)") (class "Default")
      (node (ref "C5") (pin "1") (pinfunction "1_1") (pintype "passive"))
      (node (ref "IC7") (pin "9") (pinfunction "+IN_9") (pintype "input"))
      (node (ref "R25") (pin "2") (pinfunction "2_2") (pintype "passive"))
      (node (ref "R7") (pin "1") (pinfunction "1_1") (pintype "passive"))
      (node (ref "R8") (pin "2") (pinfunction "2_2") (pintype "passive"))
    )
    (net (code "48") (name "Net-(IC7C-OUT)") (class "Default")
      (node (ref "IC7") (pin "14") (pinfunction "OUT_14") (pintype "open_collector"))
      (node (ref "R9") (pin "2") (pinfunction "2_2") (pintype "passive"))
    )
    (net (code "49") (name "Net-(IC7D-+IN)") (class "Default")
      (node (ref "IC7") (pin "11") (pinfunction "+IN_11") (pintype "input"))
      (node (ref "R2") (pin "2") (pinfunction "2_2") (pintype "passive"))
    )
    (net (code "50") (name "Net-(IC7D--IN)") (class "Default")
      (node (ref "C8") (pin "1") (pinfunction "1_1") (pintype "passive"))
      (node (ref "IC7") (pin "10") (pinfunction "-IN_10") (pintype "input"))
      (node (ref "R1") (pin "1") (pinfunction "1_1") (pintype "passive"))
    )
    (net (code "51") (name "Net-(IC7D-OUT)") (class "Default")
      (node (ref "IC7") (pin "13") (pinfunction "OUT_13") (pintype "open_collector"))
      (node (ref "R3") (pin "2") (pinfunction "2_2") (pintype "passive"))
      (node (ref "X1") (pin "21") (pinfunction "21_21") (pintype "passive"))
    )
    (net (code "52") (name "Net-(LED1-PadA)") (class "Default")
      (node (ref "LED1") (pin "A") (pinfunction "A_A") (pintype "passive"))
      (node (ref "LED2") (pin "A") (pinfunction "A_A") (pintype "passive"))
      (node (ref "LED3") (pin "A") (pinfunction "A_A") (pintype "passive"))
      (node (ref "LED4") (pin "A") (pinfunction "A_A") (pintype "passive"))
      (node (ref "LED5") (pin "A") (pinfunction "A_A") (pintype "passive"))
      (node (ref "LED7") (pin "A") (pinfunction "A_A") (pintype "passive"))
      (node (ref "R11") (pin "1") (pinfunction "1_1") (pintype "passive"))
    )
    (net (code "53") (name "Net-(LED6-C)") (class "Default")
      (node (ref "LED6") (pin "K") (pinfunction "C_K") (pintype "passive"))
      (node (ref "R4") (pin "1") (pinfunction "1_1") (pintype "passive"))
    )
    (net (code "54") (name "Net-(Q1-G)") (class "Default")
      (node (ref "Q1") (pin "1") (pinfunction "G_1") (pintype "passive"))
      (node (ref "Q3") (pin "1") (pinfunction "B_1") (pintype "passive"))
      (node (ref "R13") (pin "2") (pinfunction "2_2") (pintype "passive"))
      (node (ref "R14") (pin "2") (pinfunction "2_2") (pintype "passive"))
    )
    (net (code "55") (name "Net-(Q2-B)") (class "Default")
      (node (ref "C7") (pin "2") (pinfunction "2_2") (pintype "passive"))
      (node (ref "Q2") (pin "1") (pinfunction "B_1") (pintype "passive"))
      (node (ref "R9") (pin "1") (pinfunction "1_1") (pintype "passive"))
    )
    (net (code "56") (name "Net-(R1-Pad2)") (class "Default")
      (node (ref "R1") (pin "2") (pinfunction "2_2") (pintype "passive"))
      (node (ref "X1") (pin "22") (pinfunction "22_22") (pintype "passive"))
    )
    (net (code "57") (name "Net-(R22-Pad1)") (class "Default")
      (node (ref "R22") (pin "1") (pinfunction "1_1") (pintype "passive"))
      (node (ref "R23") (pin "1") (pinfunction "1_1") (pintype "passive"))
      (node (ref "R24") (pin "1") (pinfunction "1_1") (pintype "passive"))
    )
    (net (code "58") (name "Net-(R27-Pad2)") (class "Default")
      (node (ref "R27") (pin "2") (pinfunction "2_2") (pintype "passive"))
      (node (ref "R28") (pin "1") (pinfunction "1_1") (pintype "passive"))
    )
    (net (code "59") (name "Net-(T1A-B)") (class "Default")
      (node (ref "R38") (pin "1") (pinfunction "1_1") (pintype "passive"))
      (node (ref "R39") (pin "1") (pinfunction "1_1") (pintype "passive"))
      (node (ref "T1") (pin "2") (pinfunction "B_2") (pintype "passive"))
      (node (ref "T1") (pin "4") (pinfunction "B_4") (pintype "passive"))
      (node (ref "T1") (pin "6") (pinfunction "C1_6") (pintype "passive"))
      (node (ref "X2") (pin "2") (pinfunction "S_2") (pintype "passive"))
    )
    (net (code "60") (name "Net-(T1A-E)") (class "Default")
      (node (ref "R20") (pin "2") (pinfunction "2_2") (pintype "passive"))
      (node (ref "T1") (pin "3") (pinfunction "E_3") (pintype "passive"))
    )
    (net (code "61") (name "Net-(T1B-E)") (class "Default")
      (node (ref "R21") (pin "2") (pinfunction "2_2") (pintype "passive"))
      (node (ref "T1") (pin "1") (pinfunction "E_1") (pintype "passive"))
    )
    (net (code "62") (name "Net-(TACHO_BEL-PP)") (class "Default")
      (node (ref "TACHO_BEL") (pin "TP") (pinfunction "PP_TP") (pintype "input"))
      (node (ref "X1") (pin "24") (pinfunction "24_24") (pintype "passive"))
    )
    (net (code "63") (name "Net-(ZüNDSPULE-PP)") (class "Default")
      (node (ref "X1") (pin "16") (pinfunction "16_16") (pintype "passive"))
      (node (ref "ZüNDSPULE") (pin "TP") (pinfunction "PP_TP") (pintype "input"))
    )
    (net (code "64") (name "VCC") (class "Default")
      (node (ref "C1") (pin "1") (pinfunction "1_1") (pintype "passive"))
      (node (ref "C4") (pin "1") (pinfunction "1_1") (pintype "passive"))
      (node (ref "IC1") (pin "OUT") (pinfunction "OUT_OUT") (pintype "passive"))
      (node (ref "IC7") (pin "3") (pinfunction "V+_3") (pintype "power_in"))
      (node (ref "R11") (pin "2") (pinfunction "2_2") (pintype "passive"))
      (node (ref "R15") (pin "2") (pinfunction "2_2") (pintype "passive"))
      (node (ref "R19") (pin "1") (pinfunction "1_1") (pintype "passive"))
      (node (ref "R6") (pin "2") (pinfunction "2_2") (pintype "passive"))
    )
    (net (code "65") (name "unconnected-(IC3A-Q6-Pad7)") (class "Default")
      (node (ref "IC3") (pin "7") (pinfunction "Q6_7") (pintype "output"))
    )
    (net (code "66") (name "unconnected-(IC3A-Q7-Pad4)") (class "Default")
      (node (ref "IC3") (pin "4") (pinfunction "Q7_4") (pintype "output"))
    )
    (net (code "67") (name "unconnected-(IC3A-Q8-Pad9)") (class "Default")
      (node (ref "IC3") (pin "9") (pinfunction "Q8_9") (pintype "output"))
    )
    (net (code "68") (name "unconnected-(IC3A-Q9-Pad5)") (class "Default")
      (node (ref "IC3") (pin "5") (pinfunction "Q9_5") (pintype "output"))
    )
    (net (code "69") (name "unconnected-(IC6-CD+-Pad9)") (class "Default")
      (node (ref "IC6") (pin "9") (pinfunction "CD+_9") (pintype "passive"))
    )
    (net (code "70") (name "unconnected-(Q3-C{slash}-Pad4)") (class "Default")
      (node (ref "Q3") (pin "4") (pinfunction "C/_4") (pintype "passive"))
    )
    (net (code "71") (name "unconnected-(R26-Pad1)") (class "Default")
      (node (ref "R26") (pin "1") (pinfunction "1_1") (pintype "passive"))
    )
    (net (code "72") (name "unconnected-(R32-Pad1)") (class "Default")
      (node (ref "R32") (pin "1") (pinfunction "1_1") (pintype "passive"))
    )
    (net (code "73") (name "unconnected-(R32-Pad2)") (class "Default")
      (node (ref "R32") (pin "2") (pinfunction "2_2") (pintype "passive"))
    )
    (net (code "74") (name "unconnected-(T1A-C-Pad5)") (class "Default")
      (node (ref "T1") (pin "5") (pinfunction "C_5") (pintype "passive"))
    )
    (net (code "75") (name "unconnected-(T1B-C-Pad7)") (class "Default")
      (node (ref "T1") (pin "7") (pinfunction "C_7") (pintype "passive"))
    )
    (net (code "76") (name "unconnected-(X1-Pad20)") (class "Default")
      (node (ref "X1") (pin "20") (pinfunction "20_20") (pintype "passive"))
    )
  )
)
